# EasyEDA_DEHHANI_Yassine_Evaluation2_Elec.net
KiCad netlist of a schematic drawn in EasyEDA Pro
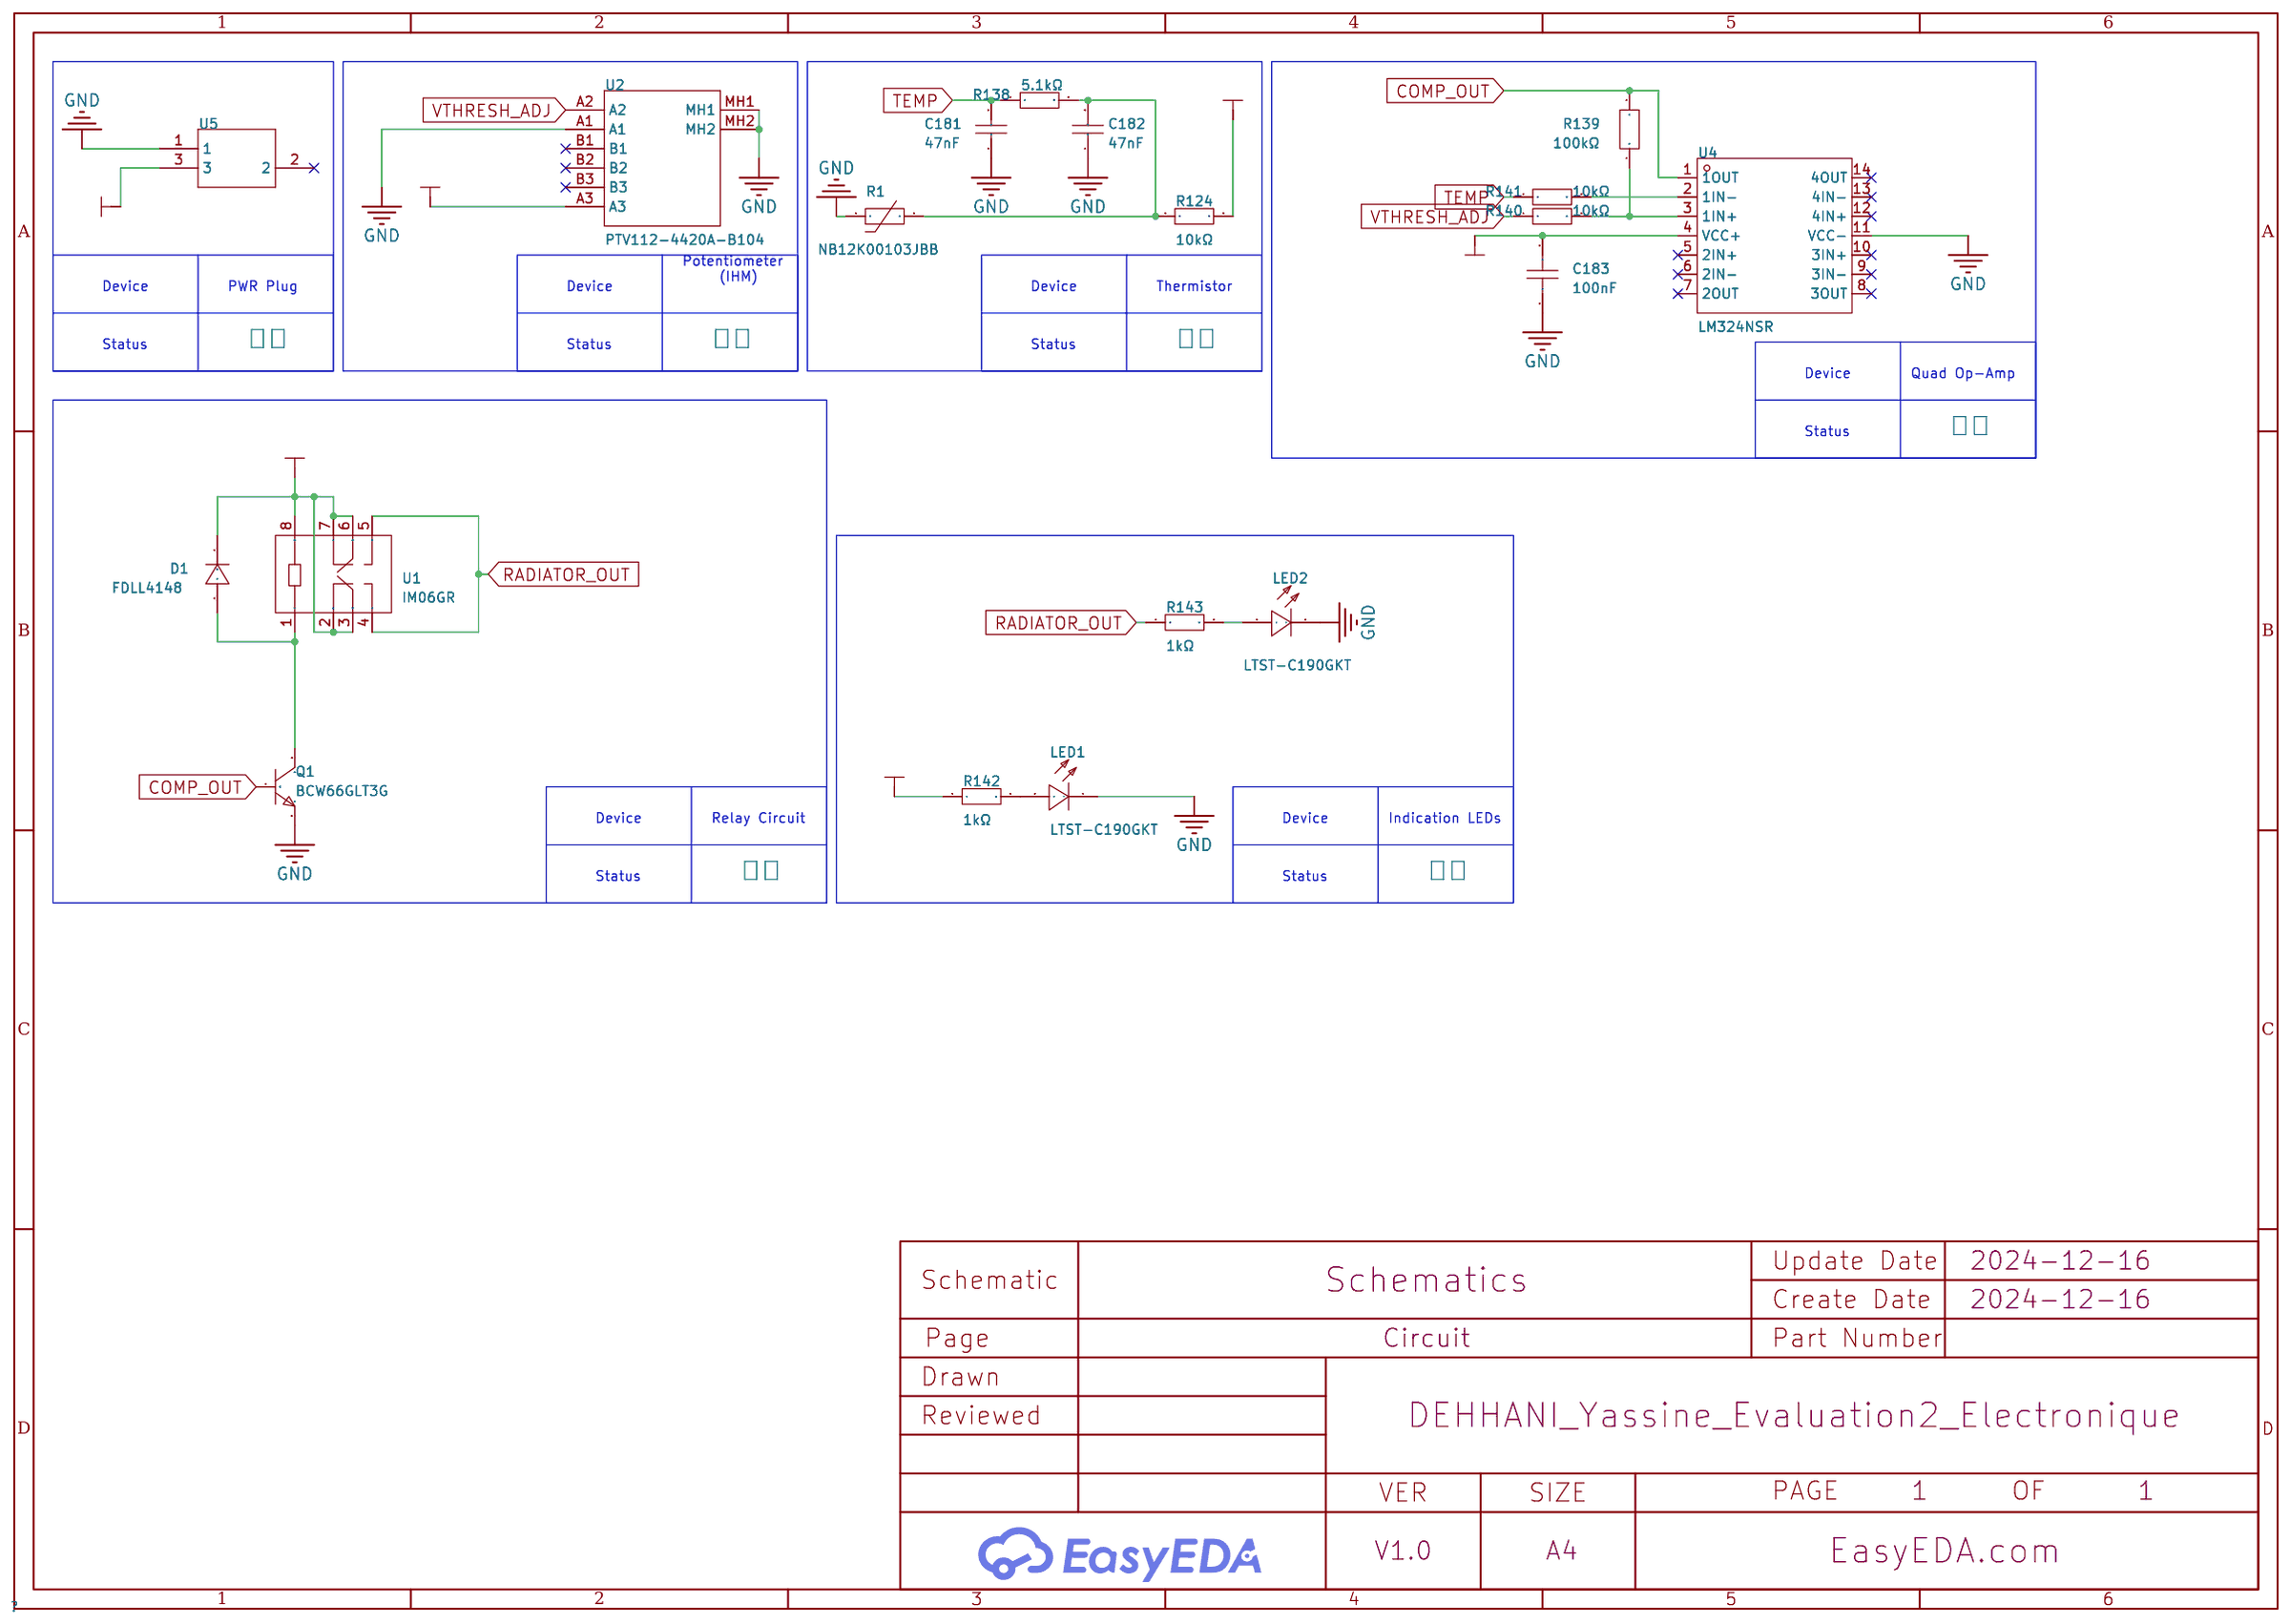
[diagram p0: schematic sheet]

(export (version "E")
  (design (tool "Eeschema 10.0.6"))
  (components
    (comp (ref "C181")
      (value "47nF")
      (footprint "easyedapro:C0402")
      (fields (field (name "Manufacturer Part") "0402B473K500NT") (field (name "Manufacturer") "FH(风华)"))
      (libsource (lib "easyedapro") (part "0402B473K500NT"))
    )
    (comp (ref "C182")
      (value "47nF")
      (footprint "easyedapro:C0402")
      (fields (field (name "Manufacturer Part") "0402B473K500NT") (field (name "Manufacturer") "FH(风华)"))
      (libsource (lib "easyedapro") (part "0402B473K500NT"))
    )
    (comp (ref "C183")
      (value "100nF")
      (footprint "easyedapro:C0805")
      (fields
        (field (name "Manufacturer Part") "CC0805KRX7R9BB104")
        (field (name "Manufacturer") "YAGEO(国巨)")
      )
      (libsource (lib "easyedapro") (part "CC0805KRX7R9BB104"))
    )
    (comp (ref "D1")
      (value "FDLL4148")
      (footprint "easyedapro:SOD-80_L3.5-W1.5-RD")
      (fields (field (name "Manufacturer") "onsemi(安森美)"))
      (libsource (lib "easyedapro") (part "FDLL4148"))
    )
    (comp (ref "LED1")
      (value "LTST-C190GKT")
      (footprint "easyedapro:LED0603-RD")
      (fields (field (name "Manufacturer") "LITEON(光宝)"))
      (libsource (lib "easyedapro") (part "LTST-C190GKT"))
    )
    (comp (ref "LED2")
      (value "LTST-C190GKT")
      (footprint "easyedapro:LED0603-RD")
      (fields (field (name "Manufacturer") "LITEON(光宝)"))
      (libsource (lib "easyedapro") (part "LTST-C190GKT"))
    )
    (comp (ref "Q1")
      (value "BCW66GLT3G")
      (footprint "easyedapro:SOT-23-3_L2.9-W1.3-P1.90-LS2.4-BR")
      (fields (field (name "Manufacturer") "onsemi(安森美)"))
      (libsource (lib "easyedapro") (part "BCW66GLT3G"))
    )
    (comp (ref "R1")
      (value "NB12K00103JBB")
      (footprint "easyedapro:R0805")
      (fields (field (name "Manufacturer") "Kyocera AVX"))
      (libsource (lib "easyedapro") (part "NB12K00103JBB"))
    )
    (comp (ref "R124")
      (value "10kΩ")
      (footprint "easyedapro:R0402")
      (fields (field (name "Manufacturer Part") "RC0402FR-0710KL") (field (name "Manufacturer") "YAGEO(国巨)"))
      (libsource (lib "easyedapro") (part "RC0402FR-0710KL"))
    )
    (comp (ref "R138")
      (value "5.1kΩ")
      (footprint "easyedapro:R0402")
      (fields (field (name "Manufacturer Part") "RK73H1ETTP5101F") (field (name "Manufacturer") "KOA"))
      (libsource (lib "easyedapro") (part "RK73H1ETTP5101F"))
    )
    (comp (ref "R139")
      (value "100kΩ")
      (footprint "easyedapro:R0805")
      (fields (field (name "Manufacturer Part") "SCR0805J100K") (field (name "Manufacturer") "VO(翔胜)"))
      (libsource (lib "easyedapro") (part "SCR0805J100K"))
    )
    (comp (ref "R140")
      (value "10kΩ")
      (footprint "easyedapro:R0805")
      (fields (field (name "Manufacturer Part") "RC0805FR-0710KL") (field (name "Manufacturer") "YAGEO(国巨)"))
      (libsource (lib "easyedapro") (part "RC0805FR-0710KL"))
    )
    (comp (ref "R141")
      (value "10kΩ")
      (footprint "easyedapro:R0805")
      (fields (field (name "Manufacturer Part") "RC0805FR-0710KL") (field (name "Manufacturer") "YAGEO(国巨)"))
      (libsource (lib "easyedapro") (part "RC0805FR-0710KL"))
    )
    (comp (ref "R142")
      (value "1kΩ")
      (footprint "easyedapro:R0805")
      (fields (field (name "Manufacturer Part") "RC0805FR-071KL") (field (name "Manufacturer") "YAGEO(国巨)"))
      (libsource (lib "easyedapro") (part "RC0805FR-071KL"))
    )
    (comp (ref "R143")
      (value "1kΩ")
      (footprint "easyedapro:R0805")
      (fields (field (name "Manufacturer Part") "RC0805FR-071KL") (field (name "Manufacturer") "YAGEO(国巨)"))
      (libsource (lib "easyedapro") (part "RC0805FR-071KL"))
    )
    (comp (ref "U1")
      (value "IM06GR")
      (footprint "easyedapro:RELAY-SMD_IMXXGR")
      (fields (field (name "Manufacturer") "TE Connectivity(泰科电子)"))
      (libsource (lib "easyedapro") (part "IM06GR"))
    )
    (comp (ref "U2")
      (value "PTV112-4420A-B104")
      (footprint "easyedapro:PTV1124420AB104")
      (libsource (lib "easyedapro") (part "PTV112-4420A-B104"))
    )
    (comp (ref "U4")
      (value "LM324NSR")
      (footprint "easyedapro:SO-14_L10.2-W5.3-P1.27-LS7.8-BL")
      (fields (field (name "Manufacturer") "TI(德州仪器)"))
      (libsource (lib "easyedapro") (part "LM324NSR"))
    )
    (comp (ref "U5")
      (value "~")
      (footprint "easyedapro:PJ1021SMTTR")
      (libsource (lib "easyedapro") (part "PJ1-021-SMT-TR"))
    )
  )
  (nets
    (net (code "1") (name "+12V") (class "Default")
      (node (ref "C183") (pin "2") (pinfunction "2_2") (pintype "unspecified"))
      (node (ref "D1") (pin "1") (pinfunction "C_1") (pintype "unspecified"))
      (node (ref "R124") (pin "2") (pinfunction "2_2") (pintype "input"))
      (node (ref "R142") (pin "1") (pinfunction "1_1") (pintype "input"))
      (node (ref "U1") (pin "2") (pinfunction "2_2") (pintype "unspecified"))
      (node (ref "U1") (pin "3") (pinfunction "3_3") (pintype "unspecified"))
      (node (ref "U1") (pin "6") (pinfunction "6_6") (pintype "unspecified"))
      (node (ref "U1") (pin "7") (pinfunction "7_7") (pintype "unspecified"))
      (node (ref "U1") (pin "8") (pinfunction "8_8") (pintype "unspecified"))
      (node (ref "U2") (pin "A3") (pinfunction "A3_A3") (pintype "bidirectional"))
      (node (ref "U4") (pin "4") (pinfunction "VCC+_4") (pintype "unspecified"))
      (node (ref "U5") (pin "3") (pinfunction "3_3") (pintype "bidirectional"))
    )
    (net (code "2") (name "COMP_OUT") (class "Default")
      (node (ref "Q1") (pin "1") (pinfunction "B_1") (pintype "input"))
      (node (ref "R139") (pin "2") (pinfunction "2_2") (pintype "unspecified"))
      (node (ref "U4") (pin "1") (pinfunction "1OUT_1") (pintype "unspecified"))
    )
    (net (code "3") (name "GND") (class "Default")
      (node (ref "C181") (pin "1") (pinfunction "1_1") (pintype "input"))
      (node (ref "C182") (pin "1") (pinfunction "1_1") (pintype "input"))
      (node (ref "C183") (pin "1") (pinfunction "1_1") (pintype "unspecified"))
      (node (ref "LED1") (pin "1") (pinfunction "-_1") (pintype "unspecified"))
      (node (ref "LED2") (pin "1") (pinfunction "-_1") (pintype "unspecified"))
      (node (ref "Q1") (pin "2") (pinfunction "E_2") (pintype "input"))
      (node (ref "R1") (pin "1") (pinfunction "1_1") (pintype "unspecified"))
      (node (ref "U2") (pin "A1") (pinfunction "A1_A1") (pintype "bidirectional"))
      (node (ref "U2") (pin "MH1") (pinfunction "MH1_MH1") (pintype "bidirectional"))
      (node (ref "U2") (pin "MH2") (pinfunction "MH2_MH2") (pintype "bidirectional"))
      (node (ref "U4") (pin "11") (pinfunction "VCC-_11") (pintype "unspecified"))
      (node (ref "U5") (pin "1") (pinfunction "1_1") (pintype "bidirectional"))
    )
    (net (code "4") (name "Net-(C182-Pad2)") (class "Default")
      (node (ref "C182") (pin "2") (pinfunction "2_2") (pintype "input"))
      (node (ref "R1") (pin "2") (pinfunction "2_2") (pintype "unspecified"))
      (node (ref "R124") (pin "1") (pinfunction "1_1") (pintype "input"))
      (node (ref "R138") (pin "2") (pinfunction "2_2") (pintype "input"))
    )
    (net (code "5") (name "Net-(D1-A)") (class "Default")
      (node (ref "D1") (pin "2") (pinfunction "A_2") (pintype "unspecified"))
      (node (ref "Q1") (pin "3") (pinfunction "C_3") (pintype "input"))
      (node (ref "U1") (pin "1") (pinfunction "1_1") (pintype "unspecified"))
    )
    (net (code "6") (name "Net-(LED1-+)") (class "Default")
      (node (ref "LED1") (pin "2") (pinfunction "+_2") (pintype "unspecified"))
      (node (ref "R142") (pin "2") (pinfunction "2_2") (pintype "input"))
    )
    (net (code "7") (name "Net-(LED2-+)") (class "Default")
      (node (ref "LED2") (pin "2") (pinfunction "+_2") (pintype "unspecified"))
      (node (ref "R143") (pin "2") (pinfunction "2_2") (pintype "input"))
    )
    (net (code "8") (name "Net-(U4-1IN+)") (class "Default")
      (node (ref "R139") (pin "1") (pinfunction "1_1") (pintype "unspecified"))
      (node (ref "R140") (pin "2") (pinfunction "2_2") (pintype "input"))
      (node (ref "U4") (pin "3") (pinfunction "1IN+_3") (pintype "unspecified"))
    )
    (net (code "9") (name "Net-(U4-1IN-)") (class "Default")
      (node (ref "R141") (pin "2") (pinfunction "2_2") (pintype "input"))
      (node (ref "U4") (pin "2") (pinfunction "1IN-_2") (pintype "unspecified"))
    )
    (net (code "10") (name "RADIATOR_OUT") (class "Default")
      (node (ref "R143") (pin "1") (pinfunction "1_1") (pintype "input"))
      (node (ref "U1") (pin "4") (pinfunction "4_4") (pintype "unspecified"))
      (node (ref "U1") (pin "5") (pinfunction "5_5") (pintype "unspecified"))
    )
    (net (code "11") (name "TEMP") (class "Default")
      (node (ref "C181") (pin "2") (pinfunction "2_2") (pintype "input"))
      (node (ref "R138") (pin "1") (pinfunction "1_1") (pintype "input"))
      (node (ref "R141") (pin "1") (pinfunction "1_1") (pintype "input"))
    )
    (net (code "12") (name "VTHRESH_ADJ") (class "Default")
      (node (ref "R140") (pin "1") (pinfunction "1_1") (pintype "input"))
      (node (ref "U2") (pin "A2") (pinfunction "A2_A2") (pintype "bidirectional"))
    )
    (net (code "13") (name "unconnected-(U2-PadB1)") (class "Default")
      (node (ref "U2") (pin "B1") (pinfunction "B1_B1") (pintype "bidirectional+no_connect"))
    )
    (net (code "14") (name "unconnected-(U2-PadB2)") (class "Default")
      (node (ref "U2") (pin "B2") (pinfunction "B2_B2") (pintype "bidirectional+no_connect"))
    )
    (net (code "15") (name "unconnected-(U2-PadB3)") (class "Default")
      (node (ref "U2") (pin "B3") (pinfunction "B3_B3") (pintype "bidirectional+no_connect"))
    )
    (net (code "16") (name "unconnected-(U4-2IN+-Pad5)") (class "Default")
      (node (ref "U4") (pin "5") (pinfunction "2IN+_5") (pintype "unspecified+no_connect"))
    )
    (net (code "17") (name "unconnected-(U4-2IN--Pad6)") (class "Default")
      (node (ref "U4") (pin "6") (pinfunction "2IN-_6") (pintype "unspecified+no_connect"))
    )
    (net (code "18") (name "unconnected-(U4-2OUT-Pad7)") (class "Default")
      (node (ref "U4") (pin "7") (pinfunction "2OUT_7") (pintype "unspecified+no_connect"))
    )
    (net (code "19") (name "unconnected-(U4-3IN+-Pad10)") (class "Default")
      (node (ref "U4") (pin "10") (pinfunction "3IN+_10") (pintype "unspecified+no_connect"))
    )
    (net (code "20") (name "unconnected-(U4-3IN--Pad9)") (class "Default")
      (node (ref "U4") (pin "9") (pinfunction "3IN-_9") (pintype "unspecified+no_connect"))
    )
    (net (code "21") (name "unconnected-(U4-3OUT-Pad8)") (class "Default")
      (node (ref "U4") (pin "8") (pinfunction "3OUT_8") (pintype "unspecified+no_connect"))
    )
    (net (code "22") (name "unconnected-(U4-4IN+-Pad12)") (class "Default")
      (node (ref "U4") (pin "12") (pinfunction "4IN+_12") (pintype "unspecified+no_connect"))
    )
    (net (code "23") (name "unconnected-(U4-4IN--Pad13)") (class "Default")
      (node (ref "U4") (pin "13") (pinfunction "4IN-_13") (pintype "unspecified+no_connect"))
    )
    (net (code "24") (name "unconnected-(U4-4OUT-Pad14)") (class "Default")
      (node (ref "U4") (pin "14") (pinfunction "4OUT_14") (pintype "unspecified+no_connect"))
    )
    (net (code "25") (name "unconnected-(U5-Pad2)") (class "Default")
      (node (ref "U5") (pin "2") (pinfunction "2_2") (pintype "bidirectional+no_connect"))
    )
  )
)
